# digital-logic___analog.net
KiCad netlist of a schematic drawn in EAGLE
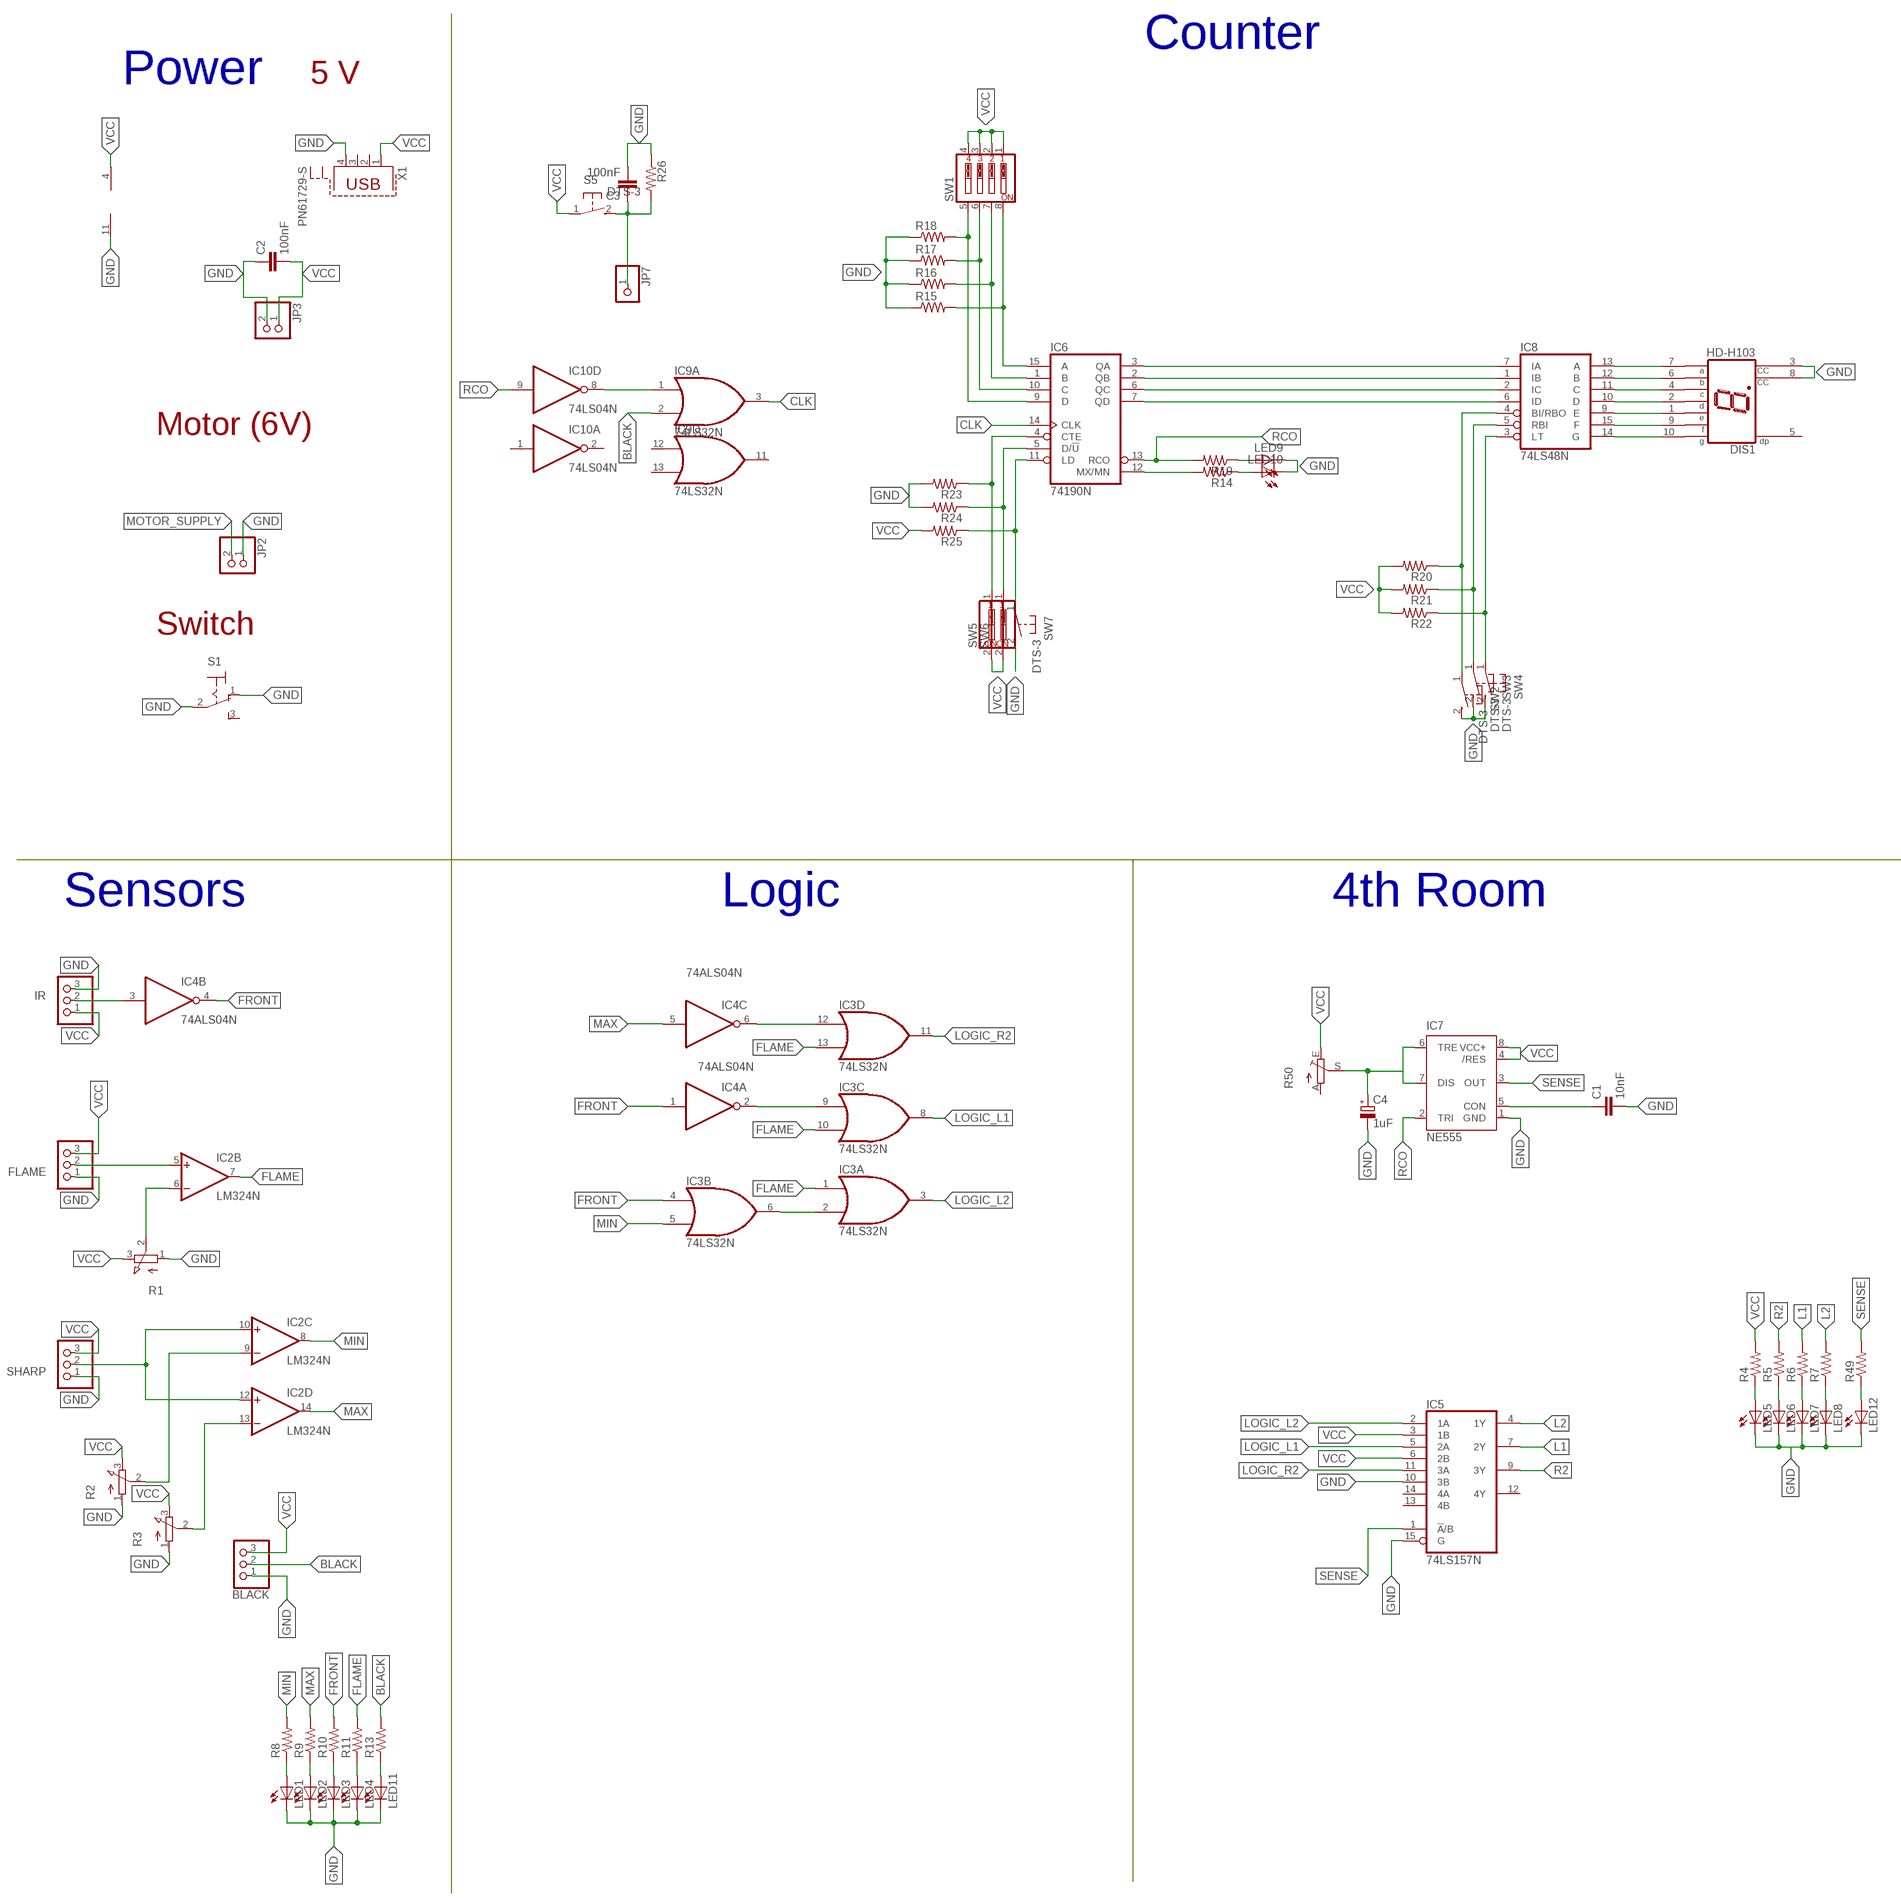
[diagram p0: schematic, sheet 1, part 1 of 2]
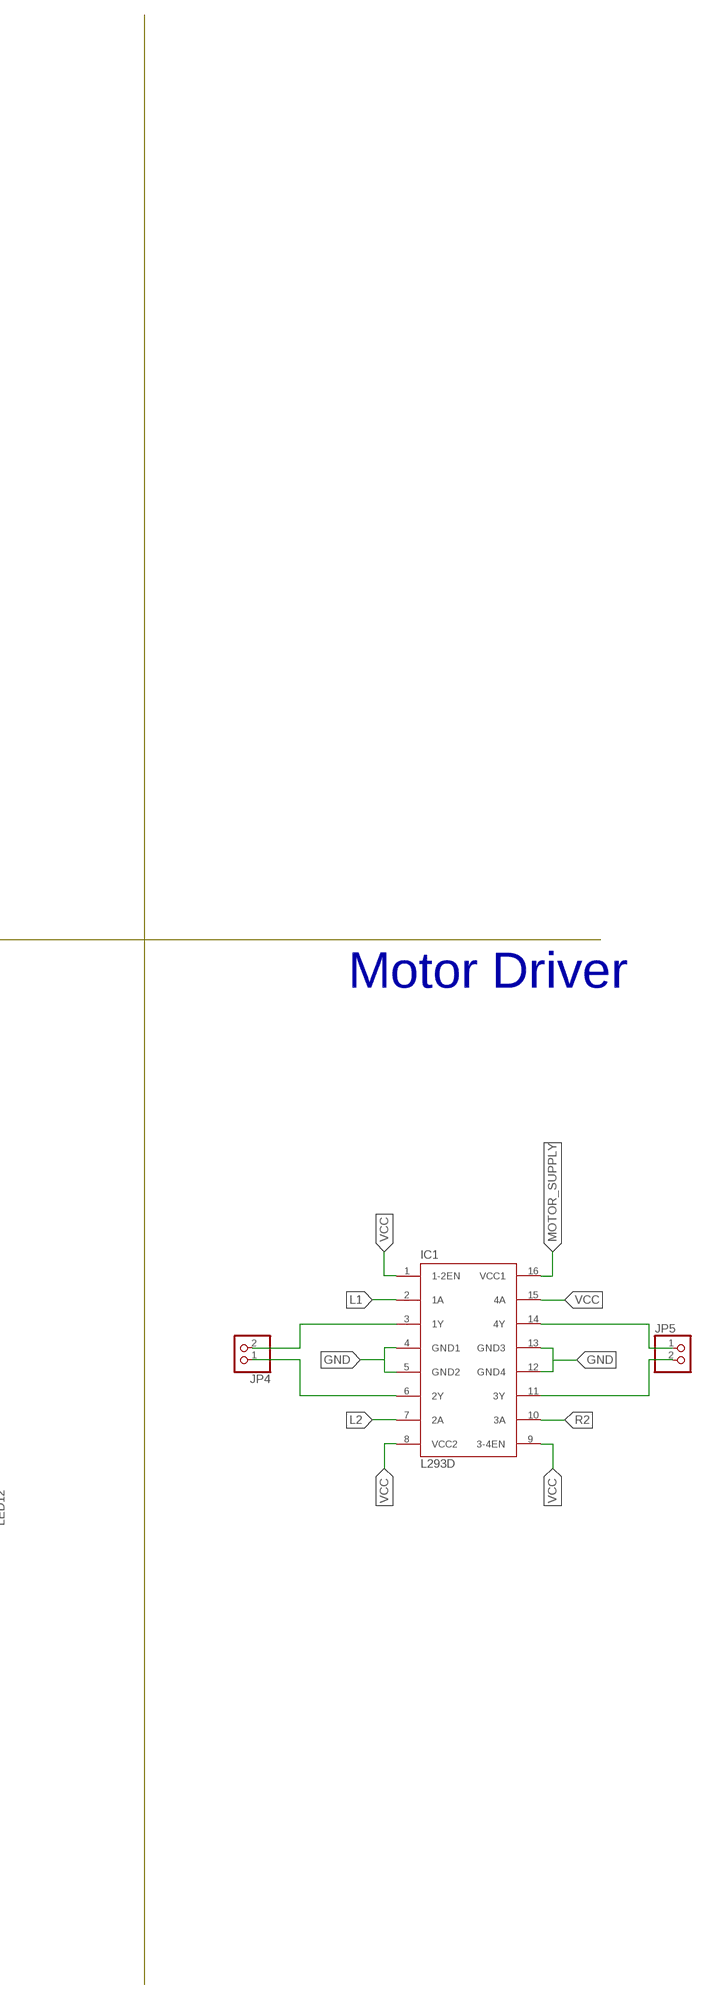
[diagram p1: schematic, sheet 1, part 2 of 2]

(export (version "E")
  (design (tool "Eeschema 10.0.6"))
  (components
    (comp (ref "BLACK")
      (value "PINHD-1X3")
      (footprint "eagle-import:1X03")
      (libsource (lib "eagle-import") (part "PINHD-1X3"))
    )
    (comp (ref "C1")
      (value "10nF")
      (footprint "eagle-import:C050-024X044")
      (libsource (lib "eagle-import") (part "C-EU050-024X044"))
    )
    (comp (ref "C2")
      (value "100nF")
      (footprint "eagle-import:C050-024X044")
      (libsource (lib "eagle-import") (part "C-EU050-024X044"))
    )
    (comp (ref "C3")
      (value "100nF")
      (footprint "eagle-import:C050-024X044")
      (libsource (lib "eagle-import") (part "C-EU050-024X044"))
    )
    (comp (ref "C4")
      (value "1uF")
      (footprint "eagle-import:E2,5-6")
      (libsource (lib "eagle-import") (part "CPOL-EUE2.5-6"))
    )
    (comp (ref "DIS1")
      (value "HD-H103")
      (footprint "eagle-import:HDSP-M")
      (libsource (lib "eagle-import") (part "HD-H103"))
    )
    (comp (ref "FLAME")
      (value "PINHD-1X3")
      (footprint "eagle-import:1X03")
      (libsource (lib "eagle-import") (part "PINHD-1X3"))
    )
    (comp (ref "IC1")
      (value "L293D")
      (footprint "eagle-import:DIL16")
      (libsource (lib "eagle-import") (part "L293D"))
    )
    (comp (ref "IC2")
      (value "LM324N")
      (footprint "eagle-import:DIL14")
      (libsource (lib "eagle-import") (part "LM324N"))
    )
    (comp (ref "IC3")
      (value "74LS32N")
      (footprint "eagle-import:DIL14")
      (libsource (lib "eagle-import") (part "7432NLS"))
    )
    (comp (ref "IC4")
      (value "74ALS04N")
      (footprint "eagle-import:DIL14")
      (libsource (lib "eagle-import") (part "7404NALS"))
    )
    (comp (ref "IC5")
      (value "74LS157N")
      (footprint "eagle-import:DIL16")
      (libsource (lib "eagle-import") (part "74157NLS"))
    )
    (comp (ref "IC6")
      (value "74190N")
      (footprint "eagle-import:DIL16")
      (libsource (lib "eagle-import") (part "74190N"))
    )
    (comp (ref "IC7")
      (value "NE555")
      (footprint "eagle-import:DIL-08")
      (fields (field (name "MF") "Arrow Electronics") (field (name "MPN") "NE555N"))
      (libsource (lib "eagle-import") (part "NE555"))
    )
    (comp (ref "IC8")
      (value "74LS48N")
      (footprint "eagle-import:DIL16")
      (libsource (lib "eagle-import") (part "7448NLS"))
    )
    (comp (ref "IC9")
      (value "74LS32N")
      (footprint "eagle-import:DIL14")
      (libsource (lib "eagle-import") (part "7432NLS"))
    )
    (comp (ref "IC10")
      (value "74LS04N")
      (footprint "eagle-import:DIL14")
      (libsource (lib "eagle-import") (part "7404NLS"))
    )
    (comp (ref "IR")
      (value "PINHD-1X3")
      (footprint "eagle-import:1X03")
      (libsource (lib "eagle-import") (part "PINHD-1X3"))
    )
    (comp (ref "JP2")
      (value "PINHD-1X2")
      (footprint "eagle-import:1X02")
      (libsource (lib "eagle-import") (part "PINHD-1X2"))
    )
    (comp (ref "JP3")
      (value "PINHD-1X2")
      (footprint "eagle-import:1X02")
      (libsource (lib "eagle-import") (part "PINHD-1X2"))
    )
    (comp (ref "JP4")
      (value "PINHD-1X2")
      (footprint "eagle-import:1X02")
      (libsource (lib "eagle-import") (part "PINHD-1X2"))
    )
    (comp (ref "JP5")
      (value "PINHD-1X2")
      (footprint "eagle-import:1X02")
      (libsource (lib "eagle-import") (part "PINHD-1X2"))
    )
    (comp (ref "JP7")
      (value "PINHD-1X1")
      (footprint "eagle-import:1X01")
      (libsource (lib "eagle-import") (part "PINHD-1X1"))
    )
    (comp (ref "LED1")
      (value "LED5MM")
      (footprint "eagle-import:LED5MM")
      (libsource (lib "eagle-import") (part "LED5MM"))
    )
    (comp (ref "LED2")
      (value "LED5MM")
      (footprint "eagle-import:LED5MM")
      (libsource (lib "eagle-import") (part "LED5MM"))
    )
    (comp (ref "LED3")
      (value "LED5MM")
      (footprint "eagle-import:LED5MM")
      (libsource (lib "eagle-import") (part "LED5MM"))
    )
    (comp (ref "LED4")
      (value "LED5MM")
      (footprint "eagle-import:LED5MM")
      (libsource (lib "eagle-import") (part "LED5MM"))
    )
    (comp (ref "LED5")
      (value "LED5MM")
      (footprint "eagle-import:LED5MM")
      (libsource (lib "eagle-import") (part "LED5MM"))
    )
    (comp (ref "LED6")
      (value "LED5MM")
      (footprint "eagle-import:LED5MM")
      (libsource (lib "eagle-import") (part "LED5MM"))
    )
    (comp (ref "LED7")
      (value "LED5MM")
      (footprint "eagle-import:LED5MM")
      (libsource (lib "eagle-import") (part "LED5MM"))
    )
    (comp (ref "LED8")
      (value "LED5MM")
      (footprint "eagle-import:LED5MM")
      (libsource (lib "eagle-import") (part "LED5MM"))
    )
    (comp (ref "LED9")
      (value "LED5MM")
      (footprint "eagle-import:LED5MM")
      (libsource (lib "eagle-import") (part "LED5MM"))
    )
    (comp (ref "LED10")
      (value "LED5MM")
      (footprint "eagle-import:LED5MM")
      (libsource (lib "eagle-import") (part "LED5MM"))
    )
    (comp (ref "LED11")
      (value "LED5MM")
      (footprint "eagle-import:LED5MM")
      (libsource (lib "eagle-import") (part "LED5MM"))
    )
    (comp (ref "LED12")
      (value "LED5MM")
      (footprint "eagle-import:LED5MM")
      (libsource (lib "eagle-import") (part "LED5MM"))
    )
    (comp (ref "R1")
      (value "3RP/1610N")
      (footprint "eagle-import:3RP_1610N")
      (libsource (lib "eagle-import") (part "3RP/1610N"))
    )
    (comp (ref "R2")
      (value "3RP/1610N")
      (footprint "eagle-import:3RP_1610N")
      (libsource (lib "eagle-import") (part "3RP/1610N"))
    )
    (comp (ref "R3")
      (value "3RP/1610N")
      (footprint "eagle-import:3RP_1610N")
      (libsource (lib "eagle-import") (part "3RP/1610N"))
    )
    (comp (ref "R4")
      (value "R-US_0204/7")
      (footprint "eagle-import:0204_7")
      (libsource (lib "eagle-import") (part "R-US_0204/7"))
    )
    (comp (ref "R5")
      (value "R-US_0204/7")
      (footprint "eagle-import:0204_7")
      (libsource (lib "eagle-import") (part "R-US_0204/7"))
    )
    (comp (ref "R6")
      (value "R-US_0204/7")
      (footprint "eagle-import:0204_7")
      (libsource (lib "eagle-import") (part "R-US_0204/7"))
    )
    (comp (ref "R7")
      (value "R-US_0204/7")
      (footprint "eagle-import:0204_7")
      (libsource (lib "eagle-import") (part "R-US_0204/7"))
    )
    (comp (ref "R8")
      (value "R-US_0204/7")
      (footprint "eagle-import:0204_7")
      (libsource (lib "eagle-import") (part "R-US_0204/7"))
    )
    (comp (ref "R9")
      (value "R-US_0204/7")
      (footprint "eagle-import:0204_7")
      (libsource (lib "eagle-import") (part "R-US_0204/7"))
    )
    (comp (ref "R10")
      (value "R-US_0204/7")
      (footprint "eagle-import:0204_7")
      (libsource (lib "eagle-import") (part "R-US_0204/7"))
    )
    (comp (ref "R11")
      (value "R-US_0204/7")
      (footprint "eagle-import:0204_7")
      (libsource (lib "eagle-import") (part "R-US_0204/7"))
    )
    (comp (ref "R13")
      (value "R-US_0204/7")
      (footprint "eagle-import:0204_7")
      (libsource (lib "eagle-import") (part "R-US_0204/7"))
    )
    (comp (ref "R14")
      (value "R-US_0204/7")
      (footprint "eagle-import:0204_7")
      (libsource (lib "eagle-import") (part "R-US_0204/7"))
    )
    (comp (ref "R15")
      (value "R-US_0204/7")
      (footprint "eagle-import:0204_7")
      (libsource (lib "eagle-import") (part "R-US_0204/7"))
    )
    (comp (ref "R16")
      (value "R-US_0204/7")
      (footprint "eagle-import:0204_7")
      (libsource (lib "eagle-import") (part "R-US_0204/7"))
    )
    (comp (ref "R17")
      (value "R-US_0204/7")
      (footprint "eagle-import:0204_7")
      (libsource (lib "eagle-import") (part "R-US_0204/7"))
    )
    (comp (ref "R18")
      (value "R-US_0204/7")
      (footprint "eagle-import:0204_7")
      (libsource (lib "eagle-import") (part "R-US_0204/7"))
    )
    (comp (ref "R19")
      (value "R-US_0204/7")
      (footprint "eagle-import:0204_7")
      (libsource (lib "eagle-import") (part "R-US_0204/7"))
    )
    (comp (ref "R20")
      (value "R-US_0204/7")
      (footprint "eagle-import:0204_7")
      (libsource (lib "eagle-import") (part "R-US_0204/7"))
    )
    (comp (ref "R21")
      (value "R-US_0204/7")
      (footprint "eagle-import:0204_7")
      (libsource (lib "eagle-import") (part "R-US_0204/7"))
    )
    (comp (ref "R22")
      (value "R-US_0204/7")
      (footprint "eagle-import:0204_7")
      (libsource (lib "eagle-import") (part "R-US_0204/7"))
    )
    (comp (ref "R23")
      (value "R-US_0204/7")
      (footprint "eagle-import:0204_7")
      (libsource (lib "eagle-import") (part "R-US_0204/7"))
    )
    (comp (ref "R24")
      (value "R-US_0204/7")
      (footprint "eagle-import:0204_7")
      (libsource (lib "eagle-import") (part "R-US_0204/7"))
    )
    (comp (ref "R25")
      (value "R-US_0204/7")
      (footprint "eagle-import:0204_7")
      (libsource (lib "eagle-import") (part "R-US_0204/7"))
    )
    (comp (ref "R26")
      (value "R-US_0204/7")
      (footprint "eagle-import:0204_7")
      (libsource (lib "eagle-import") (part "R-US_0204/7"))
    )
    (comp (ref "R49")
      (value "R-US_0204/7")
      (footprint "eagle-import:0204_7")
      (libsource (lib "eagle-import") (part "R-US_0204/7"))
    )
    (comp (ref "R50")
      (value "TRIM_EU-RJ9W")
      (footprint "eagle-import:RJ9W")
      (libsource (lib "eagle-import") (part "TRIM_EU-RJ9W"))
    )
    (comp (ref "S1")
      (value "320-916")
      (footprint "eagle-import:320-916")
      (libsource (lib "eagle-import") (part "320-916"))
    )
    (comp (ref "S5")
      (value "DTS-3")
      (footprint "eagle-import:DTS-3")
      (libsource (lib "eagle-import") (part "DTS-3"))
    )
    (comp (ref "SHARP")
      (value "PINHD-1X3")
      (footprint "eagle-import:1X03")
      (libsource (lib "eagle-import") (part "PINHD-1X3"))
    )
    (comp (ref "SW1")
      (value "SW_DIP-4")
      (footprint "eagle-import:EDG-04")
      (libsource (lib "eagle-import") (part "SW_DIP-4"))
    )
    (comp (ref "SW2")
      (value "DTS-3")
      (footprint "eagle-import:DTS-3")
      (libsource (lib "eagle-import") (part "DTS-3"))
    )
    (comp (ref "SW3")
      (value "DTS-3")
      (footprint "eagle-import:DTS-3")
      (libsource (lib "eagle-import") (part "DTS-3"))
    )
    (comp (ref "SW4")
      (value "DTS-3")
      (footprint "eagle-import:DTS-3")
      (libsource (lib "eagle-import") (part "DTS-3"))
    )
    (comp (ref "SW5")
      (value "SW_DIP-1")
      (footprint "eagle-import:EDG-01")
      (libsource (lib "eagle-import") (part "SW_DIP-1"))
    )
    (comp (ref "SW6")
      (value "SW_DIP-1")
      (footprint "eagle-import:EDG-01")
      (libsource (lib "eagle-import") (part "SW_DIP-1"))
    )
    (comp (ref "SW7")
      (value "DTS-3")
      (footprint "eagle-import:DTS-3")
      (libsource (lib "eagle-import") (part "DTS-3"))
    )
    (comp (ref "X1")
      (value "PN61729-S")
      (footprint "eagle-import:PN61729-S")
      (libsource (lib "eagle-import") (part "PN61729-S"))
    )
  )
  (nets
    (net (code "1") (name "BLACK") (class "Default")
      (node (ref "BLACK") (pin "2") (pinfunction "2_2") (pintype "passive"))
      (node (ref "IC9") (pin "2") (pinfunction "I1_2") (pintype "input"))
      (node (ref "R13") (pin "2") (pinfunction "2_2") (pintype "passive"))
    )
    (net (code "2") (name "CLK") (class "Default")
      (node (ref "IC6") (pin "14") (pinfunction "CLK_14") (pintype "input"))
      (node (ref "IC9") (pin "3") (pinfunction "O_3") (pintype "output"))
    )
    (net (code "3") (name "FLAME") (class "Default")
      (node (ref "IC2") (pin "7") (pinfunction "OUT_7") (pintype "output"))
      (node (ref "IC3") (pin "1") (pinfunction "I0_1") (pintype "input"))
      (node (ref "IC3") (pin "10") (pinfunction "I1_10") (pintype "input"))
      (node (ref "IC3") (pin "13") (pinfunction "I1_13") (pintype "input"))
      (node (ref "R11") (pin "2") (pinfunction "2_2") (pintype "passive"))
    )
    (net (code "4") (name "FRONT") (class "Default")
      (node (ref "IC3") (pin "4") (pinfunction "I0_4") (pintype "input"))
      (node (ref "IC4") (pin "1") (pinfunction "I_1") (pintype "input"))
      (node (ref "IC4") (pin "4") (pinfunction "O_4") (pintype "output"))
      (node (ref "R10") (pin "2") (pinfunction "2_2") (pintype "passive"))
    )
    (net (code "5") (name "GND") (class "Default")
      (node (ref "BLACK") (pin "1") (pinfunction "1_1") (pintype "passive"))
      (node (ref "C1") (pin "2") (pinfunction "2_2") (pintype "passive"))
      (node (ref "C2") (pin "1") (pinfunction "1_1") (pintype "passive"))
      (node (ref "C3") (pin "2") (pinfunction "2_2") (pintype "passive"))
      (node (ref "C4") (pin "-") (pinfunction "-_-") (pintype "passive"))
      (node (ref "DIS1") (pin "3") (pinfunction "CC_3") (pintype "passive"))
      (node (ref "DIS1") (pin "8") (pinfunction "CC_8") (pintype "passive"))
      (node (ref "FLAME") (pin "1") (pinfunction "1_1") (pintype "passive"))
      (node (ref "IC1") (pin "12") (pinfunction "GND4_12") (pintype "power_in"))
      (node (ref "IC1") (pin "13") (pinfunction "GND3_13") (pintype "power_in"))
      (node (ref "IC1") (pin "4") (pinfunction "GND1_4") (pintype "power_in"))
      (node (ref "IC1") (pin "5") (pinfunction "GND2_5") (pintype "power_in"))
      (node (ref "IC2") (pin "11") (pinfunction "V-_11") (pintype "power_in"))
      (node (ref "IC5") (pin "10") (pinfunction "3B_10") (pintype "input"))
      (node (ref "IC5") (pin "15") (pinfunction "G_15") (pintype "input"))
      (node (ref "IC7") (pin "1") (pinfunction "GND_1") (pintype "power_in"))
      (node (ref "IR") (pin "3") (pinfunction "3_3") (pintype "passive"))
      (node (ref "JP2") (pin "1") (pinfunction "1_1") (pintype "passive"))
      (node (ref "JP3") (pin "2") (pinfunction "2_2") (pintype "passive"))
      (node (ref "LED1") (pin "K") (pinfunction "C_K") (pintype "passive"))
      (node (ref "LED10") (pin "K") (pinfunction "C_K") (pintype "passive"))
      (node (ref "LED11") (pin "K") (pinfunction "C_K") (pintype "passive"))
      (node (ref "LED12") (pin "K") (pinfunction "C_K") (pintype "passive"))
      (node (ref "LED2") (pin "K") (pinfunction "C_K") (pintype "passive"))
      (node (ref "LED3") (pin "K") (pinfunction "C_K") (pintype "passive"))
      (node (ref "LED4") (pin "K") (pinfunction "C_K") (pintype "passive"))
      (node (ref "LED5") (pin "K") (pinfunction "C_K") (pintype "passive"))
      (node (ref "LED6") (pin "K") (pinfunction "C_K") (pintype "passive"))
      (node (ref "LED7") (pin "K") (pinfunction "C_K") (pintype "passive"))
      (node (ref "LED8") (pin "K") (pinfunction "C_K") (pintype "passive"))
      (node (ref "LED9") (pin "K") (pinfunction "C_K") (pintype "passive"))
      (node (ref "R1") (pin "1") (pinfunction "A_1") (pintype "passive"))
      (node (ref "R15") (pin "1") (pinfunction "1_1") (pintype "passive"))
      (node (ref "R16") (pin "1") (pinfunction "1_1") (pintype "passive"))
      (node (ref "R17") (pin "1") (pinfunction "1_1") (pintype "passive"))
      (node (ref "R18") (pin "1") (pinfunction "1_1") (pintype "passive"))
      (node (ref "R2") (pin "1") (pinfunction "A_1") (pintype "passive"))
      (node (ref "R23") (pin "2") (pinfunction "2_2") (pintype "passive"))
      (node (ref "R24") (pin "2") (pinfunction "2_2") (pintype "passive"))
      (node (ref "R26") (pin "1") (pinfunction "1_1") (pintype "passive"))
      (node (ref "R3") (pin "1") (pinfunction "A_1") (pintype "passive"))
      (node (ref "S1") (pin "1") (pinfunction "O_1") (pintype "passive"))
      (node (ref "S1") (pin "2") (pinfunction "P_2") (pintype "passive"))
      (node (ref "SHARP") (pin "1") (pinfunction "1_1") (pintype "passive"))
      (node (ref "SW2") (pin "2") (pinfunction "2_2") (pintype "passive"))
      (node (ref "SW3") (pin "2") (pinfunction "2_2") (pintype "passive"))
      (node (ref "SW4") (pin "2") (pinfunction "2_2") (pintype "passive"))
      (node (ref "SW7") (pin "2") (pinfunction "2_2") (pintype "passive"))
      (node (ref "X1") (pin "4") (pinfunction "4_4") (pintype "passive"))
    )
    (net (code "6") (name "L1") (class "Default")
      (node (ref "IC1") (pin "2") (pinfunction "1A_2") (pintype "input"))
      (node (ref "IC5") (pin "7") (pinfunction "2Y_7") (pintype "output"))
      (node (ref "R6") (pin "2") (pinfunction "2_2") (pintype "passive"))
    )
    (net (code "7") (name "L2") (class "Default")
      (node (ref "IC1") (pin "7") (pinfunction "2A_7") (pintype "input"))
      (node (ref "IC5") (pin "4") (pinfunction "1Y_4") (pintype "output"))
      (node (ref "R7") (pin "2") (pinfunction "2_2") (pintype "passive"))
    )
    (net (code "8") (name "LOGIC_L1") (class "Default")
      (node (ref "IC3") (pin "8") (pinfunction "O_8") (pintype "output"))
      (node (ref "IC5") (pin "5") (pinfunction "2A_5") (pintype "input"))
    )
    (net (code "9") (name "LOGIC_L2") (class "Default")
      (node (ref "IC3") (pin "3") (pinfunction "O_3") (pintype "output"))
      (node (ref "IC5") (pin "2") (pinfunction "1A_2") (pintype "input"))
    )
    (net (code "10") (name "LOGIC_R2") (class "Default")
      (node (ref "IC3") (pin "11") (pinfunction "O_11") (pintype "output"))
      (node (ref "IC5") (pin "11") (pinfunction "3A_11") (pintype "input"))
    )
    (net (code "11") (name "MAX") (class "Default")
      (node (ref "IC2") (pin "14") (pinfunction "OUT_14") (pintype "output"))
      (node (ref "IC4") (pin "5") (pinfunction "I_5") (pintype "input"))
      (node (ref "R9") (pin "2") (pinfunction "2_2") (pintype "passive"))
    )
    (net (code "12") (name "MIN") (class "Default")
      (node (ref "IC2") (pin "8") (pinfunction "OUT_8") (pintype "output"))
      (node (ref "IC3") (pin "5") (pinfunction "I1_5") (pintype "input"))
      (node (ref "R8") (pin "2") (pinfunction "2_2") (pintype "passive"))
    )
    (net (code "13") (name "MOTOR_SUPPLY") (class "Default")
      (node (ref "IC1") (pin "16") (pinfunction "VCC1_16") (pintype "power_in"))
      (node (ref "JP2") (pin "2") (pinfunction "2_2") (pintype "passive"))
    )
    (net (code "14") (name "Net-(C3-Pad1)") (class "Default")
      (node (ref "C3") (pin "1") (pinfunction "1_1") (pintype "passive"))
      (node (ref "JP7") (pin "1") (pinfunction "1_1") (pintype "passive"))
      (node (ref "R26") (pin "2") (pinfunction "2_2") (pintype "passive"))
      (node (ref "S5") (pin "2") (pinfunction "2_2") (pintype "passive"))
    )
    (net (code "15") (name "Net-(DIS1-A)") (class "Default")
      (node (ref "DIS1") (pin "7") (pinfunction "A_7") (pintype "passive"))
      (node (ref "IC8") (pin "13") (pinfunction "A_13") (pintype "output"))
    )
    (net (code "16") (name "Net-(DIS1-B)") (class "Default")
      (node (ref "DIS1") (pin "6") (pinfunction "B_6") (pintype "passive"))
      (node (ref "IC8") (pin "12") (pinfunction "B_12") (pintype "output"))
    )
    (net (code "17") (name "Net-(DIS1-C)") (class "Default")
      (node (ref "DIS1") (pin "4") (pinfunction "C_4") (pintype "passive"))
      (node (ref "IC8") (pin "11") (pinfunction "C_11") (pintype "output"))
    )
    (net (code "18") (name "Net-(DIS1-D)") (class "Default")
      (node (ref "DIS1") (pin "2") (pinfunction "D_2") (pintype "passive"))
      (node (ref "IC8") (pin "10") (pinfunction "D_10") (pintype "output"))
    )
    (net (code "19") (name "Net-(DIS1-E)") (class "Default")
      (node (ref "DIS1") (pin "1") (pinfunction "E_1") (pintype "passive"))
      (node (ref "IC8") (pin "9") (pinfunction "E_9") (pintype "output"))
    )
    (net (code "20") (name "Net-(DIS1-F)") (class "Default")
      (node (ref "DIS1") (pin "9") (pinfunction "F_9") (pintype "passive"))
      (node (ref "IC8") (pin "15") (pinfunction "F_15") (pintype "output"))
    )
    (net (code "21") (name "Net-(DIS1-G)") (class "Default")
      (node (ref "DIS1") (pin "10") (pinfunction "G_10") (pintype "passive"))
      (node (ref "IC8") (pin "14") (pinfunction "G_14") (pintype "output"))
    )
    (net (code "22") (name "Net-(IC1-1Y)") (class "Default")
      (node (ref "IC1") (pin "3") (pinfunction "1Y_3") (pintype "output"))
      (node (ref "JP4") (pin "2") (pinfunction "2_2") (pintype "passive"))
    )
    (net (code "23") (name "Net-(IC1-2Y)") (class "Default")
      (node (ref "IC1") (pin "6") (pinfunction "2Y_6") (pintype "output"))
      (node (ref "JP4") (pin "1") (pinfunction "1_1") (pintype "passive"))
    )
    (net (code "24") (name "Net-(IC1-3Y)") (class "Default")
      (node (ref "IC1") (pin "11") (pinfunction "3Y_11") (pintype "output"))
      (node (ref "JP5") (pin "2") (pinfunction "2_2") (pintype "passive"))
    )
    (net (code "25") (name "Net-(IC1-4Y)") (class "Default")
      (node (ref "IC1") (pin "14") (pinfunction "4Y_14") (pintype "output"))
      (node (ref "JP5") (pin "1") (pinfunction "1_1") (pintype "passive"))
    )
    (net (code "26") (name "Net-(IC2B-+IN)") (class "Default")
      (node (ref "FLAME") (pin "2") (pinfunction "2_2") (pintype "passive"))
      (node (ref "IC2") (pin "5") (pinfunction "+IN_5") (pintype "input"))
    )
    (net (code "27") (name "Net-(IC2B--IN)") (class "Default")
      (node (ref "IC2") (pin "6") (pinfunction "-IN_6") (pintype "input"))
      (node (ref "R1") (pin "2") (pinfunction "S_2") (pintype "passive"))
    )
    (net (code "28") (name "Net-(IC2C-+IN)") (class "Default")
      (node (ref "IC2") (pin "10") (pinfunction "+IN_10") (pintype "input"))
      (node (ref "IC2") (pin "12") (pinfunction "+IN_12") (pintype "input"))
      (node (ref "SHARP") (pin "2") (pinfunction "2_2") (pintype "passive"))
    )
    (net (code "29") (name "Net-(IC2C--IN)") (class "Default")
      (node (ref "IC2") (pin "9") (pinfunction "-IN_9") (pintype "input"))
      (node (ref "R2") (pin "2") (pinfunction "S_2") (pintype "passive"))
    )
    (net (code "30") (name "Net-(IC2D--IN)") (class "Default")
      (node (ref "IC2") (pin "13") (pinfunction "-IN_13") (pintype "input"))
      (node (ref "R3") (pin "2") (pinfunction "S_2") (pintype "passive"))
    )
    (net (code "31") (name "Net-(IC3A-I1)") (class "Default")
      (node (ref "IC3") (pin "2") (pinfunction "I1_2") (pintype "input"))
      (node (ref "IC3") (pin "6") (pinfunction "O_6") (pintype "output"))
    )
    (net (code "32") (name "Net-(IC3C-I0)") (class "Default")
      (node (ref "IC3") (pin "9") (pinfunction "I0_9") (pintype "input"))
      (node (ref "IC4") (pin "2") (pinfunction "O_2") (pintype "output"))
    )
    (net (code "33") (name "Net-(IC3D-I0)") (class "Default")
      (node (ref "IC3") (pin "12") (pinfunction "I0_12") (pintype "input"))
      (node (ref "IC4") (pin "6") (pinfunction "O_6") (pintype "output"))
    )
    (net (code "34") (name "Net-(IC4B-I)") (class "Default")
      (node (ref "IC4") (pin "3") (pinfunction "I_3") (pintype "input"))
      (node (ref "IR") (pin "2") (pinfunction "2_2") (pintype "passive"))
    )
    (net (code "35") (name "Net-(IC6A-A)") (class "Default")
      (node (ref "IC6") (pin "15") (pinfunction "A_15") (pintype "input"))
      (node (ref "R15") (pin "2") (pinfunction "2_2") (pintype "passive"))
      (node (ref "SW1") (pin "8") (pinfunction "8_8") (pintype "passive"))
    )
    (net (code "36") (name "Net-(IC6A-B)") (class "Default")
      (node (ref "IC6") (pin "1") (pinfunction "B_1") (pintype "input"))
      (node (ref "R16") (pin "2") (pinfunction "2_2") (pintype "passive"))
      (node (ref "SW1") (pin "7") (pinfunction "7_7") (pintype "passive"))
    )
    (net (code "37") (name "Net-(IC6A-C)") (class "Default")
      (node (ref "IC6") (pin "10") (pinfunction "C_10") (pintype "input"))
      (node (ref "R17") (pin "2") (pinfunction "2_2") (pintype "passive"))
      (node (ref "SW1") (pin "6") (pinfunction "6_6") (pintype "passive"))
    )
    (net (code "38") (name "Net-(IC6A-CTE)") (class "Default")
      (node (ref "IC6") (pin "4") (pinfunction "CTE_4") (pintype "input"))
      (node (ref "R23") (pin "1") (pinfunction "1_1") (pintype "passive"))
      (node (ref "SW5") (pin "1") (pinfunction "1_1") (pintype "passive"))
    )
    (net (code "39") (name "Net-(IC6A-D)") (class "Default")
      (node (ref "IC6") (pin "9") (pinfunction "D_9") (pintype "input"))
      (node (ref "R18") (pin "2") (pinfunction "2_2") (pintype "passive"))
      (node (ref "SW1") (pin "5") (pinfunction "5_5") (pintype "passive"))
    )
    (net (code "40") (name "Net-(IC6A-D{slash}~{U})") (class "Default")
      (node (ref "IC6") (pin "5") (pinfunction "D/~{U}_5") (pintype "input"))
      (node (ref "R24") (pin "1") (pinfunction "1_1") (pintype "passive"))
      (node (ref "SW6") (pin "1") (pinfunction "1_1") (pintype "passive"))
    )
    (net (code "41") (name "Net-(IC6A-LD)") (class "Default")
      (node (ref "IC6") (pin "11") (pinfunction "LD_11") (pintype "input"))
      (node (ref "R25") (pin "1") (pinfunction "1_1") (pintype "passive"))
      (node (ref "SW7") (pin "1") (pinfunction "1_1") (pintype "passive"))
    )
    (net (code "42") (name "Net-(IC6A-MX{slash}MN)") (class "Default")
      (node (ref "IC6") (pin "12") (pinfunction "MX/MN_12") (pintype "output"))
      (node (ref "R14") (pin "2") (pinfunction "2_2") (pintype "passive"))
    )
    (net (code "43") (name "Net-(IC6A-QA)") (class "Default")
      (node (ref "IC6") (pin "3") (pinfunction "QA_3") (pintype "output"))
      (node (ref "IC8") (pin "7") (pinfunction "IA_7") (pintype "input"))
    )
    (net (code "44") (name "Net-(IC6A-QB)") (class "Default")
      (node (ref "IC6") (pin "2") (pinfunction "QB_2") (pintype "output"))
      (node (ref "IC8") (pin "1") (pinfunction "IB_1") (pintype "input"))
    )
    (net (code "45") (name "Net-(IC6A-QC)") (class "Default")
      (node (ref "IC6") (pin "6") (pinfunction "QC_6") (pintype "output"))
      (node (ref "IC8") (pin "2") (pinfunction "IC_2") (pintype "input"))
    )
    (net (code "46") (name "Net-(IC6A-QD)") (class "Default")
      (node (ref "IC6") (pin "7") (pinfunction "QD_7") (pintype "output"))
      (node (ref "IC8") (pin "6") (pinfunction "ID_6") (pintype "input"))
    )
    (net (code "47") (name "Net-(IC7-CON)") (class "Default")
      (node (ref "C1") (pin "1") (pinfunction "1_1") (pintype "passive"))
      (node (ref "IC7") (pin "5") (pinfunction "CON_5") (pintype "input"))
    )
    (net (code "48") (name "Net-(IC7-DIS)") (class "Default")
      (node (ref "C4") (pin "+") (pinfunction "+_+") (pintype "passive"))
      (node (ref "IC7") (pin "6") (pinfunction "TRE_6") (pintype "input"))
      (node (ref "IC7") (pin "7") (pinfunction "DIS_7") (pintype "input"))
      (node (ref "R50") (pin "S") (pinfunction "S_S") (pintype "passive"))
    )
    (net (code "49") (name "Net-(IC8A-BI{slash}RBO)") (class "Default")
      (node (ref "IC8") (pin "4") (pinfunction "BI/RBO_4") (pintype "input"))
      (node (ref "R20") (pin "1") (pinfunction "1_1") (pintype "passive"))
      (node (ref "SW2") (pin "1") (pinfunction "1_1") (pintype "passive"))
    )
    (net (code "50") (name "Net-(IC8A-LT)") (class "Default")
      (node (ref "IC8") (pin "3") (pinfunction "LT_3") (pintype "input"))
      (node (ref "R22") (pin "1") (pinfunction "1_1") (pintype "passive"))
      (node (ref "SW4") (pin "1") (pinfunction "1_1") (pintype "passive"))
    )
    (net (code "51") (name "Net-(IC8A-RBI)") (class "Default")
      (node (ref "IC8") (pin "5") (pinfunction "RBI_5") (pintype "input"))
      (node (ref "R21") (pin "1") (pinfunction "1_1") (pintype "passive"))
      (node (ref "SW3") (pin "1") (pinfunction "1_1") (pintype "passive"))
    )
    (net (code "52") (name "Net-(IC10D-O)") (class "Default")
      (node (ref "IC10") (pin "8") (pinfunction "O_8") (pintype "output"))
      (node (ref "IC9") (pin "1") (pinfunction "I0_1") (pintype "input"))
    )
    (net (code "53") (name "Net-(LED1-PadA)") (class "Default")
      (node (ref "LED1") (pin "A") (pinfunction "A_A") (pintype "passive"))
      (node (ref "R8") (pin "1") (pinfunction "1_1") (pintype "passive"))
    )
    (net (code "54") (name "Net-(LED2-PadA)") (class "Default")
      (node (ref "LED2") (pin "A") (pinfunction "A_A") (pintype "passive"))
      (node (ref "R9") (pin "1") (pinfunction "1_1") (pintype "passive"))
    )
    (net (code "55") (name "Net-(LED3-PadA)") (class "Default")
      (node (ref "LED3") (pin "A") (pinfunction "A_A") (pintype "passive"))
      (node (ref "R10") (pin "1") (pinfunction "1_1") (pintype "passive"))
    )
    (net (code "56") (name "Net-(LED4-PadA)") (class "Default")
      (node (ref "LED4") (pin "A") (pinfunction "A_A") (pintype "passive"))
      (node (ref "R11") (pin "1") (pinfunction "1_1") (pintype "passive"))
    )
    (net (code "57") (name "Net-(LED5-PadA)") (class "Default")
      (node (ref "LED5") (pin "A") (pinfunction "A_A") (pintype "passive"))
      (node (ref "R4") (pin "1") (pinfunction "1_1") (pintype "passive"))
    )
    (net (code "58") (name "Net-(LED6-PadA)") (class "Default")
      (node (ref "LED6") (pin "A") (pinfunction "A_A") (pintype "passive"))
      (node (ref "R5") (pin "1") (pinfunction "1_1") (pintype "passive"))
    )
    (net (code "59") (name "Net-(LED7-PadA)") (class "Default")
      (node (ref "LED7") (pin "A") (pinfunction "A_A") (pintype "passive"))
      (node (ref "R6") (pin "1") (pinfunction "1_1") (pintype "passive"))
    )
    (net (code "60") (name "Net-(LED8-PadA)") (class "Default")
      (node (ref "LED8") (pin "A") (pinfunction "A_A") (pintype "passive"))
      (node (ref "R7") (pin "1") (pinfunction "1_1") (pintype "passive"))
    )
    (net (code "61") (name "Net-(LED9-PadA)") (class "Default")
      (node (ref "LED9") (pin "A") (pinfunction "A_A") (pintype "passive"))
      (node (ref "R19") (pin "1") (pinfunction "1_1") (pintype "passive"))
    )
    (net (code "62") (name "Net-(LED10-PadA)") (class "Default")
      (node (ref "LED10") (pin "A") (pinfunction "A_A") (pintype "passive"))
      (node (ref "R14") (pin "1") (pinfunction "1_1") (pintype "passive"))
    )
    (net (code "63") (name "Net-(LED11-PadA)") (class "Default")
      (node (ref "LED11") (pin "A") (pinfunction "A_A") (pintype "passive"))
      (node (ref "R13") (pin "1") (pinfunction "1_1") (pintype "passive"))
    )
    (net (code "64") (name "Net-(LED12-PadA)") (class "Default")
      (node (ref "LED12") (pin "A") (pinfunction "A_A") (pintype "passive"))
      (node (ref "R49") (pin "1") (pinfunction "1_1") (pintype "passive"))
    )
    (net (code "65") (name "R2") (class "Default")
      (node (ref "IC1") (pin "10") (pinfunction "3A_10") (pintype "input"))
      (node (ref "IC5") (pin "9") (pinfunction "3Y_9") (pintype "output"))
      (node (ref "R5") (pin "2") (pinfunction "2_2") (pintype "passive"))
    )
    (net (code "66") (name "RCO") (class "Default")
      (node (ref "IC10") (pin "9") (pinfunction "I_9") (pintype "input"))
      (node (ref "IC6") (pin "13") (pinfunction "RCO_13") (pintype "output"))
      (node (ref "IC7") (pin "2") (pinfunction "TRI_2") (pintype "input"))
      (node (ref "R19") (pin "2") (pinfunction "2_2") (pintype "passive"))
    )
    (net (code "67") (name "SENSE") (class "Default")
      (node (ref "IC5") (pin "1") (pinfunction "~{A}/B_1") (pintype "input"))
      (node (ref "IC7") (pin "3") (pinfunction "OUT_3") (pintype "output"))
      (node (ref "R49") (pin "2") (pinfunction "2_2") (pintype "passive"))
    )
    (net (code "68") (name "VCC") (class "Default")
      (node (ref "BLACK") (pin "3") (pinfunction "3_3") (pintype "passive"))
      (node (ref "C2") (pin "2") (pinfunction "2_2") (pintype "passive"))
      (node (ref "FLAME") (pin "3") (pinfunction "3_3") (pintype "passive"))
      (node (ref "IC1") (pin "1") (pinfunction "1-2EN_1") (pintype "input"))
      (node (ref "IC1") (pin "15") (pinfunction "4A_15") (pintype "input"))
      (node (ref "IC1") (pin "8") (pinfunction "VCC2_8") (pintype "power_in"))
      (node (ref "IC1") (pin "9") (pinfunction "3-4EN_9") (pintype "input"))
      (node (ref "IC2") (pin "4") (pinfunction "V+_4") (pintype "power_in"))
      (node (ref "IC5") (pin "3") (pinfunction "1B_3") (pintype "input"))
      (node (ref "IC5") (pin "6") (pinfunction "2B_6") (pintype "input"))
      (node (ref "IC7") (pin "4") (pinfunction "/RES_4") (pintype "input"))
      (node (ref "IC7") (pin "8") (pinfunction "VCC+_8") (pintype "power_in"))
      (node (ref "IR") (pin "1") (pinfunction "1_1") (pintype "passive"))
      (node (ref "JP3") (pin "1") (pinfunction "1_1") (pintype "passive"))
      (node (ref "R1") (pin "3") (pinfunction "E_3") (pintype "passive"))
      (node (ref "R2") (pin "3") (pinfunction "E_3") (pintype "passive"))
      (node (ref "R20") (pin "2") (pinfunction "2_2") (pintype "passive"))
      (node (ref "R21") (pin "2") (pinfunction "2_2") (pintype "passive"))
      (node (ref "R22") (pin "2") (pinfunction "2_2") (pintype "passive"))
      (node (ref "R25") (pin "2") (pinfunction "2_2") (pintype "passive"))
      (node (ref "R3") (pin "3") (pinfunction "E_3") (pintype "passive"))
      (node (ref "R4") (pin "2") (pinfunction "2_2") (pintype "passive"))
      (node (ref "R50") (pin "E") (pinfunction "E_E") (pintype "passive"))
      (node (ref "S5") (pin "1") (pinfunction "1_1") (pintype "passive"))
      (node (ref "SHARP") (pin "3") (pinfunction "3_3") (pintype "passive"))
      (node (ref "SW1") (pin "1") (pinfunction "1_1") (pintype "passive"))
      (node (ref "SW1") (pin "2") (pinfunction "2_2") (pintype "passive"))
      (node (ref "SW1") (pin "3") (pinfunction "3_3") (pintype "passive"))
      (node (ref "SW1") (pin "4") (pinfunction "4_4") (pintype "passive"))
      (node (ref "SW5") (pin "2") (pinfunction "2_2") (pintype "passive"))
      (node (ref "SW6") (pin "2") (pinfunction "2_2") (pintype "passive"))
      (node (ref "X1") (pin "1") (pinfunction "1_1") (pintype "passive"))
    )
    (net (code "69") (name "unconnected-(DIS1-DP-Pad5)") (class "Default")
      (node (ref "DIS1") (pin "5") (pinfunction "DP_5") (pintype "passive"))
    )
    (net (code "70") (name "unconnected-(IC5A-4A-Pad14)") (class "Default")
      (node (ref "IC5") (pin "14") (pinfunction "4A_14") (pintype "input"))
    )
    (net (code "71") (name "unconnected-(IC5A-4B-Pad13)") (class "Default")
      (node (ref "IC5") (pin "13") (pinfunction "4B_13") (pintype "input"))
    )
    (net (code "72") (name "unconnected-(IC5A-4Y-Pad12)") (class "Default")
      (node (ref "IC5") (pin "12") (pinfunction "4Y_12") (pintype "output"))
    )
    (net (code "73") (name "unconnected-(IC9D-I0-Pad12)") (class "Default")
      (node (ref "IC9") (pin "12") (pinfunction "I0_12") (pintype "input"))
    )
    (net (code "74") (name "unconnected-(IC9D-I1-Pad13)") (class "Default")
      (node (ref "IC9") (pin "13") (pinfunction "I1_13") (pintype "input"))
    )
    (net (code "75") (name "unconnected-(IC9D-O-Pad11)") (class "Default")
      (node (ref "IC9") (pin "11") (pinfunction "O_11") (pintype "output"))
    )
    (net (code "76") (name "unconnected-(IC10A-I-Pad1)") (class "Default")
      (node (ref "IC10") (pin "1") (pinfunction "I_1") (pintype "input"))
    )
    (net (code "77") (name "unconnected-(IC10A-O-Pad2)") (class "Default")
      (node (ref "IC10") (pin "2") (pinfunction "O_2") (pintype "output"))
    )
    (net (code "78") (name "unconnected-(R50-PadA)") (class "Default")
      (node (ref "R50") (pin "A") (pinfunction "A_A") (pintype "passive"))
    )
    (net (code "79") (name "unconnected-(S1-S-Pad3)") (class "Default")
      (node (ref "S1") (pin "3") (pinfunction "S_3") (pintype "passive"))
    )
    (net (code "80") (name "unconnected-(X1-Pad2)") (class "Default")
      (node (ref "X1") (pin "2") (pinfunction "2_2") (pintype "passive"))
    )
    (net (code "81") (name "unconnected-(X1-Pad3)") (class "Default")
      (node (ref "X1") (pin "3") (pinfunction "3_3") (pintype "passive"))
    )
    (net (code "82") (name "unconnected-(X1-PadS1)") (class "Default")
      (node (ref "X1") (pin "S1") (pinfunction "S1_S1") (pintype "passive"))
    )
    (net (code "83") (name "unconnected-(X1-PadS2)") (class "Default")
      (node (ref "X1") (pin "S2") (pinfunction "S2_S2") (pintype "passive"))
    )
  )
)
